# 04-VIDEO_OUT.net
KiCad netlist of a schematic drawn in Altium Designer
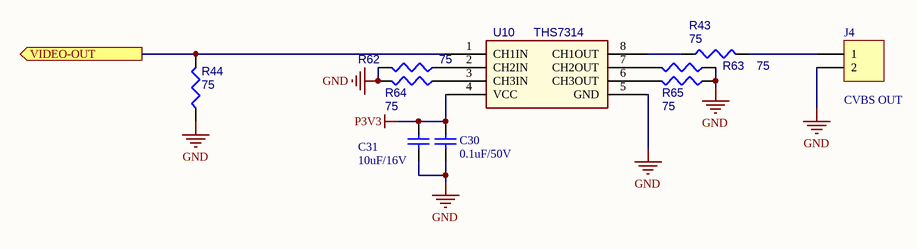
[diagram p0: 04-VIDEO_OUT.SchDoc]

(export (version "E")
  (design (tool "Eeschema 10.0.6"))
  (components
    (comp (ref "C30")
      (value "0.1uF/50V")
      (footprint "0402")
      (description "Capacitor")
      (fields (field (name "PUBLISHER") "Altium Limited"))
      (libsource (lib "Miscellaneous Devices") (part "Cap"))
    )
    (comp (ref "C31")
      (value "10uF/16V")
      (footprint "0805")
      (description "Capacitor")
      (fields (field (name "PUBLISHER") "Altium Limited"))
      (libsource (lib "Miscellaneous Devices") (part "Cap"))
    )
    (comp (ref "J4")
      (value "CVBS OUT")
      (footprint "CONN-2.0-SMD-2P-V")
      (description "Header, 2-Pin")
      (fields (field (name "PUBLISHER") "Altium Limited"))
      (libsource (lib "Miscellaneous Connectors") (part "Header 2"))
    )
    (comp (ref "R43")
      (value "75")
      (fields (field (name "PART NUMBER") "SD02810028L"))
      (libsource (lib "*") (part "R"))
    )
    (comp (ref "R44")
      (value "75")
      (fields (field (name "PART NUMBER") "SD02810028L"))
      (libsource (lib "*") (part "R"))
    )
    (comp (ref "R62")
      (value "75")
      (fields (field (name "PART NUMBER") "SD02810028L"))
      (libsource (lib "*") (part "R"))
    )
    (comp (ref "R63")
      (value "75")
      (fields (field (name "PART NUMBER") "SD02810028L"))
      (libsource (lib "*") (part "R"))
    )
    (comp (ref "R64")
      (value "75")
      (fields (field (name "PART NUMBER") "SD02810028L"))
      (libsource (lib "*") (part "R"))
    )
    (comp (ref "R65")
      (value "75")
      (fields (field (name "PART NUMBER") "SD02810028L"))
      (libsource (lib "*") (part "R"))
    )
    (comp (ref "U10") (value "THS7314") (libsource (lib "*") (part "THS7314")))
  )
  (nets
    (net (code "1") (name "/VIDEO-OUT") (class "Default")
      (node (ref "R44") (pin "2") (pinfunction "2_2") (pintype "passive"))
      (node (ref "U10") (pin "1") (pinfunction "CH1IN_1") (pintype "passive"))
    )
    (net (code "2") (name "GND") (class "Default")
      (node (ref "C30") (pin "2") (pinfunction "2_2") (pintype "passive"))
      (node (ref "C31") (pin "2") (pinfunction "2_2") (pintype "passive"))
      (node (ref "J4") (pin "2") (pinfunction "2_2") (pintype "passive"))
      (node (ref "R44") (pin "1") (pinfunction "1_1") (pintype "passive"))
      (node (ref "R62") (pin "2") (pinfunction "2_2") (pintype "passive"))
      (node (ref "R63") (pin "1") (pinfunction "1_1") (pintype "passive"))
      (node (ref "R64") (pin "2") (pinfunction "2_2") (pintype "passive"))
      (node (ref "R65") (pin "1") (pinfunction "1_1") (pintype "passive"))
      (node (ref "U10") (pin "5") (pinfunction "GND_5") (pintype "passive"))
    )
    (net (code "3") (name "Net-(J4-Pad1)") (class "Default")
      (node (ref "J4") (pin "1") (pinfunction "1_1") (pintype "passive"))
      (node (ref "R43") (pin "2") (pinfunction "2_2") (pintype "passive"))
    )
    (net (code "4") (name "Net-(U10-CH1OUT)") (class "Default")
      (node (ref "R43") (pin "1") (pinfunction "1_1") (pintype "passive"))
      (node (ref "U10") (pin "8") (pinfunction "CH1OUT_8") (pintype "passive"))
    )
    (net (code "5") (name "Net-(U10-CH2IN)") (class "Default")
      (node (ref "R62") (pin "1") (pinfunction "1_1") (pintype "passive"))
      (node (ref "U10") (pin "2") (pinfunction "CH2IN_2") (pintype "passive"))
    )
    (net (code "6") (name "Net-(U10-CH2OUT)") (class "Default")
      (node (ref "R63") (pin "2") (pinfunction "2_2") (pintype "passive"))
      (node (ref "U10") (pin "7") (pinfunction "CH2OUT_7") (pintype "passive"))
    )
    (net (code "7") (name "Net-(U10-CH3IN)") (class "Default")
      (node (ref "R64") (pin "1") (pinfunction "1_1") (pintype "passive"))
      (node (ref "U10") (pin "3") (pinfunction "CH3IN_3") (pintype "passive"))
    )
    (net (code "8") (name "Net-(U10-CH3OUT)") (class "Default")
      (node (ref "R65") (pin "2") (pinfunction "2_2") (pintype "passive"))
      (node (ref "U10") (pin "6") (pinfunction "CH3OUT_6") (pintype "passive"))
    )
    (net (code "9") (name "P3V3") (class "Default")
      (node (ref "C30") (pin "1") (pinfunction "1_1") (pintype "passive"))
      (node (ref "C31") (pin "1") (pinfunction "1_1") (pintype "passive"))
      (node (ref "U10") (pin "4") (pinfunction "VCC_4") (pintype "passive"))
    )
  )
)
